# Host_Bypass_FPGA_3V3.net
KiCad netlist of a schematic drawn in Altium Designer
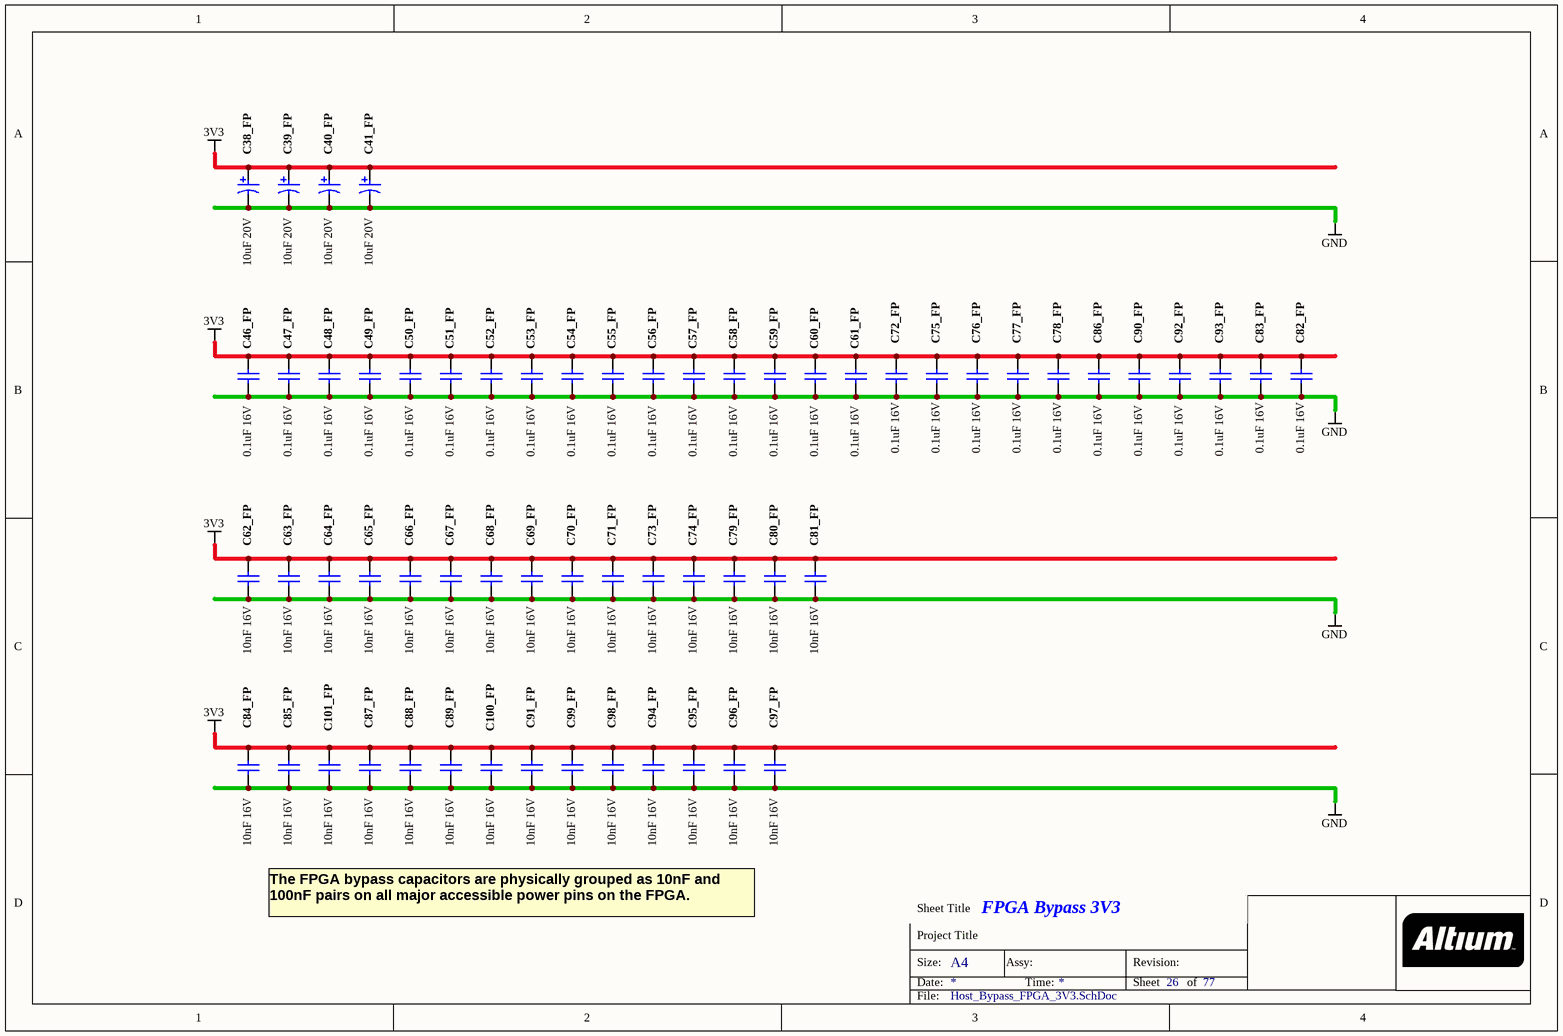
[diagram p0: Host_Bypass_FPGA_3V3.SchDoc]

(export (version "E")
  (design (tool "Eeschema 10.0.6"))
  (components
    (comp (ref "C38_FP")
      (value "10uF 20V")
      (footprint "CAPC3528-STAR")
      (description "Capacitor, Tantalum, 10uF 10% 20V MCCT-B (3528)")
      (fields (field (name "TOLERANCE") "10 %"))
      (libsource (lib "altium-import") (part "root_0_CAP-P_"))
    )
    (comp (ref "C39_FP")
      (value "10uF 20V")
      (footprint "CAPC3528-STAR")
      (description "Capacitor, Tantalum, 10uF 10% 20V MCCT-B (3528)")
      (fields (field (name "TOLERANCE") "10 %"))
      (libsource (lib "altium-import") (part "root_0_CAP-P_"))
    )
    (comp (ref "C40_FP")
      (value "10uF 20V")
      (footprint "CAPC3528-STAR")
      (description "Capacitor, Tantalum, 10uF 10% 20V MCCT-B (3528)")
      (fields (field (name "TOLERANCE") "10 %"))
      (libsource (lib "altium-import") (part "root_0_CAP-P_"))
    )
    (comp (ref "C41_FP")
      (value "10uF 20V")
      (footprint "CAPC3528-STAR")
      (description "Capacitor, Tantalum, 10uF 10% 20V MCCT-B (3528)")
      (fields (field (name "TOLERANCE") "10 %"))
      (libsource (lib "altium-import") (part "root_0_CAP-P_"))
    )
    (comp (ref "C46_FP")
      (value "0.1uF 16V")
      (footprint "CAPC1005-STAR")
      (description "Capacitor, Ceramic, 0.1uF 10% 16V 0402 (1005) X7R")
      (fields (field (name "TOLERANCE") "10 %"))
      (libsource (lib "altium-import") (part "root_0_mirrored_CAP-NP_"))
    )
    (comp (ref "C47_FP")
      (value "0.1uF 16V")
      (footprint "CAPC1005-STAR")
      (description "Capacitor, Ceramic, 0.1uF 10% 16V 0402 (1005) X7R")
      (fields (field (name "TOLERANCE") "10 %"))
      (libsource (lib "altium-import") (part "root_0_mirrored_CAP-NP_"))
    )
    (comp (ref "C48_FP")
      (value "0.1uF 16V")
      (footprint "CAPC1005-STAR")
      (description "Capacitor, Ceramic, 0.1uF 10% 16V 0402 (1005) X7R")
      (fields (field (name "TOLERANCE") "10 %"))
      (libsource (lib "altium-import") (part "root_0_mirrored_CAP-NP_"))
    )
    (comp (ref "C49_FP")
      (value "0.1uF 16V")
      (footprint "CAPC1005-STAR")
      (description "Capacitor, Ceramic, 0.1uF 10% 16V 0402 (1005) X7R")
      (fields (field (name "TOLERANCE") "10 %"))
      (libsource (lib "altium-import") (part "root_0_mirrored_CAP-NP_"))
    )
    (comp (ref "C50_FP")
      (value "0.1uF 16V")
      (footprint "CAPC1005-STAR")
      (description "Capacitor, Ceramic, 0.1uF 10% 16V 0402 (1005) X7R")
      (fields (field (name "TOLERANCE") "10 %"))
      (libsource (lib "altium-import") (part "root_0_mirrored_CAP-NP_"))
    )
    (comp (ref "C51_FP")
      (value "0.1uF 16V")
      (footprint "CAPC1005-STAR")
      (description "Capacitor, Ceramic, 0.1uF 10% 16V 0402 (1005) X7R")
      (fields (field (name "TOLERANCE") "10 %"))
      (libsource (lib "altium-import") (part "root_0_mirrored_CAP-NP_"))
    )
    (comp (ref "C52_FP")
      (value "0.1uF 16V")
      (footprint "CAPC1005-STAR")
      (description "Capacitor, Ceramic, 0.1uF 10% 16V 0402 (1005) X7R")
      (fields (field (name "TOLERANCE") "10 %"))
      (libsource (lib "altium-import") (part "root_0_mirrored_CAP-NP_"))
    )
    (comp (ref "C53_FP")
      (value "0.1uF 16V")
      (footprint "CAPC1005-STAR")
      (description "Capacitor, Ceramic, 0.1uF 10% 16V 0402 (1005) X7R")
      (fields (field (name "TOLERANCE") "10 %"))
      (libsource (lib "altium-import") (part "root_0_mirrored_CAP-NP_"))
    )
    (comp (ref "C54_FP")
      (value "0.1uF 16V")
      (footprint "CAPC1005-STAR")
      (description "Capacitor, Ceramic, 0.1uF 10% 16V 0402 (1005) X7R")
      (fields (field (name "TOLERANCE") "10 %"))
      (libsource (lib "altium-import") (part "root_0_mirrored_CAP-NP_"))
    )
    (comp (ref "C55_FP")
      (value "0.1uF 16V")
      (footprint "CAPC1005-STAR")
      (description "Capacitor, Ceramic, 0.1uF 10% 16V 0402 (1005) X7R")
      (fields (field (name "TOLERANCE") "10 %"))
      (libsource (lib "altium-import") (part "root_0_mirrored_CAP-NP_"))
    )
    (comp (ref "C56_FP")
      (value "0.1uF 16V")
      (footprint "CAPC1005-STAR")
      (description "Capacitor, Ceramic, 0.1uF 10% 16V 0402 (1005) X7R")
      (fields (field (name "TOLERANCE") "10 %"))
      (libsource (lib "altium-import") (part "root_0_mirrored_CAP-NP_"))
    )
    (comp (ref "C57_FP")
      (value "0.1uF 16V")
      (footprint "CAPC1005-STAR")
      (description "Capacitor, Ceramic, 0.1uF 10% 16V 0402 (1005) X7R")
      (fields (field (name "TOLERANCE") "10 %"))
      (libsource (lib "altium-import") (part "root_0_mirrored_CAP-NP_"))
    )
    (comp (ref "C58_FP")
      (value "0.1uF 16V")
      (footprint "CAPC1005-STAR")
      (description "Capacitor, Ceramic, 0.1uF 10% 16V 0402 (1005) X7R")
      (fields (field (name "TOLERANCE") "10 %"))
      (libsource (lib "altium-import") (part "root_0_mirrored_CAP-NP_"))
    )
    (comp (ref "C59_FP")
      (value "0.1uF 16V")
      (footprint "CAPC1005-STAR")
      (description "Capacitor, Ceramic, 0.1uF 10% 16V 0402 (1005) X7R")
      (fields (field (name "TOLERANCE") "10 %"))
      (libsource (lib "altium-import") (part "root_0_mirrored_CAP-NP_"))
    )
    (comp (ref "C60_FP")
      (value "0.1uF 16V")
      (footprint "CAPC1005-STAR")
      (description "Capacitor, Ceramic, 0.1uF 10% 16V 0402 (1005) X7R")
      (fields (field (name "TOLERANCE") "10 %"))
      (libsource (lib "altium-import") (part "root_0_mirrored_CAP-NP_"))
    )
    (comp (ref "C61_FP")
      (value "0.1uF 16V")
      (footprint "CAPC1005-STAR")
      (description "Capacitor, Ceramic, 0.1uF 10% 16V 0402 (1005) X7R")
      (fields (field (name "TOLERANCE") "10 %"))
      (libsource (lib "altium-import") (part "root_0_mirrored_CAP-NP_"))
    )
    (comp (ref "C62_FP")
      (value "10nF 16V")
      (footprint "CAPC1005-STAR")
      (description "Capacitor, Ceramic, 10nF 10% 16V 0402 (1005) X7R")
      (fields (field (name "TOLERANCE") "10 %"))
      (libsource (lib "altium-import") (part "root_0_CAP-NP_"))
    )
    (comp (ref "C63_FP")
      (value "10nF 16V")
      (footprint "CAPC1005-STAR")
      (description "Capacitor, Ceramic, 10nF 10% 16V 0402 (1005) X7R")
      (fields (field (name "TOLERANCE") "10 %"))
      (libsource (lib "altium-import") (part "root_0_CAP-NP_"))
    )
    (comp (ref "C64_FP")
      (value "10nF 16V")
      (footprint "CAPC1005-STAR")
      (description "Capacitor, Ceramic, 10nF 10% 16V 0402 (1005) X7R")
      (fields (field (name "TOLERANCE") "10 %"))
      (libsource (lib "altium-import") (part "root_0_CAP-NP_"))
    )
    (comp (ref "C65_FP")
      (value "10nF 16V")
      (footprint "CAPC1005-STAR")
      (description "Capacitor, Ceramic, 10nF 10% 16V 0402 (1005) X7R")
      (fields (field (name "TOLERANCE") "10 %"))
      (libsource (lib "altium-import") (part "root_0_CAP-NP_"))
    )
    (comp (ref "C66_FP")
      (value "10nF 16V")
      (footprint "CAPC1005-STAR")
      (description "Capacitor, Ceramic, 10nF 10% 16V 0402 (1005) X7R")
      (fields (field (name "TOLERANCE") "10 %"))
      (libsource (lib "altium-import") (part "root_0_CAP-NP_"))
    )
    (comp (ref "C67_FP")
      (value "10nF 16V")
      (footprint "CAPC1005-STAR")
      (description "Capacitor, Ceramic, 10nF 10% 16V 0402 (1005) X7R")
      (fields (field (name "TOLERANCE") "10 %"))
      (libsource (lib "altium-import") (part "root_0_CAP-NP_"))
    )
    (comp (ref "C68_FP")
      (value "10nF 16V")
      (footprint "CAPC1005-STAR")
      (description "Capacitor, Ceramic, 10nF 10% 16V 0402 (1005) X7R")
      (fields (field (name "TOLERANCE") "10 %"))
      (libsource (lib "altium-import") (part "root_0_CAP-NP_"))
    )
    (comp (ref "C69_FP")
      (value "10nF 16V")
      (footprint "CAPC1005-STAR")
      (description "Capacitor, Ceramic, 10nF 10% 16V 0402 (1005) X7R")
      (fields (field (name "TOLERANCE") "10 %"))
      (libsource (lib "altium-import") (part "root_0_CAP-NP_"))
    )
    (comp (ref "C70_FP")
      (value "10nF 16V")
      (footprint "CAPC1005-STAR")
      (description "Capacitor, Ceramic, 10nF 10% 16V 0402 (1005) X7R")
      (fields (field (name "TOLERANCE") "10 %"))
      (libsource (lib "altium-import") (part "root_0_CAP-NP_"))
    )
    (comp (ref "C71_FP")
      (value "10nF 16V")
      (footprint "CAPC1005-STAR")
      (description "Capacitor, Ceramic, 10nF 10% 16V 0402 (1005) X7R")
      (fields (field (name "TOLERANCE") "10 %"))
      (libsource (lib "altium-import") (part "root_0_CAP-NP_"))
    )
    (comp (ref "C72_FP")
      (value "0.1uF 16V")
      (footprint "CAPC1005-STAR")
      (description "Capacitor, Ceramic, 0.1uF 10% 16V 0402 (1005) X7R")
      (fields (field (name "TOLERANCE") "10 %"))
      (libsource (lib "AltiumDesignLibrary") (part "CAP-NP"))
    )
    (comp (ref "C73_FP")
      (value "10nF 16V")
      (footprint "CAPC1005-STAR")
      (description "Capacitor, Ceramic, 10nF 10% 16V 0402 (1005) X7R")
      (fields (field (name "TOLERANCE") "10 %"))
      (libsource (lib "altium-import") (part "root_0_CAP-NP_"))
    )
    (comp (ref "C74_FP")
      (value "10nF 16V")
      (footprint "CAPC1005-STAR")
      (description "Capacitor, Ceramic, 10nF 10% 16V 0402 (1005) X7R")
      (fields (field (name "TOLERANCE") "10 %"))
      (libsource (lib "altium-import") (part "root_0_CAP-NP_"))
    )
    (comp (ref "C75_FP")
      (value "0.1uF 16V")
      (footprint "CAPC1005-STAR")
      (description "Capacitor, Ceramic, 0.1uF 10% 16V 0402 (1005) X7R")
      (fields (field (name "TOLERANCE") "10 %"))
      (libsource (lib "AltiumDesignLibrary") (part "CAP-NP"))
    )
    (comp (ref "C76_FP")
      (value "0.1uF 16V")
      (footprint "CAPC1005-STAR")
      (description "Capacitor, Ceramic, 0.1uF 10% 16V 0402 (1005) X7R")
      (fields (field (name "TOLERANCE") "10 %"))
      (libsource (lib "AltiumDesignLibrary") (part "CAP-NP"))
    )
    (comp (ref "C77_FP")
      (value "0.1uF 16V")
      (footprint "CAPC1005-STAR")
      (description "Capacitor, Ceramic, 0.1uF 10% 16V 0402 (1005) X7R")
      (fields (field (name "TOLERANCE") "10 %"))
      (libsource (lib "AltiumDesignLibrary") (part "CAP-NP"))
    )
    (comp (ref "C78_FP")
      (value "0.1uF 16V")
      (footprint "CAPC1005-STAR")
      (description "Capacitor, Ceramic, 0.1uF 10% 16V 0402 (1005) X7R")
      (fields (field (name "TOLERANCE") "10 %"))
      (libsource (lib "AltiumDesignLibrary") (part "CAP-NP"))
    )
    (comp (ref "C79_FP")
      (value "10nF 16V")
      (footprint "CAPC1005-STAR")
      (description "Capacitor, Ceramic, 10nF 10% 16V 0402 (1005) X7R")
      (fields (field (name "TOLERANCE") "10 %"))
      (libsource (lib "altium-import") (part "root_0_CAP-NP_"))
    )
    (comp (ref "C80_FP")
      (value "10nF 16V")
      (footprint "CAPC1005-STAR")
      (description "Capacitor, Ceramic, 10nF 10% 16V 0402 (1005) X7R")
      (fields (field (name "TOLERANCE") "10 %"))
      (libsource (lib "altium-import") (part "root_0_CAP-NP_"))
    )
    (comp (ref "C81_FP")
      (value "10nF 16V")
      (footprint "CAPC1005-STAR")
      (description "Capacitor, Ceramic, 10nF 10% 16V 0402 (1005) X7R")
      (fields (field (name "TOLERANCE") "10 %"))
      (libsource (lib "altium-import") (part "root_0_CAP-NP_"))
    )
    (comp (ref "C82_FP")
      (value "0.1uF 16V")
      (footprint "CAPC1005-STAR")
      (description "Capacitor, Ceramic, 0.1uF 10% 16V 0402 (1005) X7R")
      (fields (field (name "TOLERANCE") "10 %"))
      (libsource (lib "AltiumDesignLibrary") (part "CAP-NP"))
    )
    (comp (ref "C83_FP")
      (value "0.1uF 16V")
      (footprint "CAPC1005-STAR")
      (description "Capacitor, Ceramic, 0.1uF 10% 16V 0402 (1005) X7R")
      (fields (field (name "TOLERANCE") "10 %"))
      (libsource (lib "AltiumDesignLibrary") (part "CAP-NP"))
    )
    (comp (ref "C84_FP")
      (value "10nF 16V")
      (footprint "CAPC1005-STAR")
      (description "Capacitor, Ceramic, 10nF 10% 16V 0402 (1005) X7R")
      (fields (field (name "TOLERANCE") "10 %"))
      (libsource (lib "altium-import") (part "root_0_CAP-NP_"))
    )
    (comp (ref "C85_FP")
      (value "10nF 16V")
      (footprint "CAPC1005-STAR")
      (description "Capacitor, Ceramic, 10nF 10% 16V 0402 (1005) X7R")
      (fields (field (name "TOLERANCE") "10 %"))
      (libsource (lib "altium-import") (part "root_0_CAP-NP_"))
    )
    (comp (ref "C86_FP")
      (value "0.1uF 16V")
      (footprint "CAPC1005-STAR")
      (description "Capacitor, Ceramic, 0.1uF 10% 16V 0402 (1005) X7R")
      (fields (field (name "TOLERANCE") "10 %"))
      (libsource (lib "AltiumDesignLibrary") (part "CAP-NP"))
    )
    (comp (ref "C87_FP")
      (value "10nF 16V")
      (footprint "CAPC1005-STAR")
      (description "Capacitor, Ceramic, 10nF 10% 16V 0402 (1005) X7R")
      (fields (field (name "TOLERANCE") "10 %"))
      (libsource (lib "altium-import") (part "root_0_CAP-NP_"))
    )
    (comp (ref "C88_FP")
      (value "10nF 16V")
      (footprint "CAPC1005-STAR")
      (description "Capacitor, Ceramic, 10nF 10% 16V 0402 (1005) X7R")
      (fields (field (name "TOLERANCE") "10 %"))
      (libsource (lib "altium-import") (part "root_0_CAP-NP_"))
    )
    (comp (ref "C89_FP")
      (value "10nF 16V")
      (footprint "CAPC1005-STAR")
      (description "Capacitor, Ceramic, 10nF 10% 16V 0402 (1005) X7R")
      (fields (field (name "TOLERANCE") "10 %"))
      (libsource (lib "altium-import") (part "root_0_CAP-NP_"))
    )
    (comp (ref "C90_FP")
      (value "0.1uF 16V")
      (footprint "CAPC1005-STAR")
      (description "Capacitor, Ceramic, 0.1uF 10% 16V 0402 (1005) X7R")
      (fields (field (name "TOLERANCE") "10 %"))
      (libsource (lib "AltiumDesignLibrary") (part "CAP-NP"))
    )
    (comp (ref "C91_FP")
      (value "10nF 16V")
      (footprint "CAPC1005-STAR")
      (description "Capacitor, Ceramic, 10nF 10% 16V 0402 (1005) X7R")
      (fields (field (name "TOLERANCE") "10 %"))
      (libsource (lib "altium-import") (part "root_0_CAP-NP_"))
    )
    (comp (ref "C92_FP")
      (value "0.1uF 16V")
      (footprint "CAPC1005-STAR")
      (description "Capacitor, Ceramic, 0.1uF 10% 16V 0402 (1005) X7R")
      (fields (field (name "TOLERANCE") "10 %"))
      (libsource (lib "AltiumDesignLibrary") (part "CAP-NP"))
    )
    (comp (ref "C93_FP")
      (value "0.1uF 16V")
      (footprint "CAPC1005-STAR")
      (description "Capacitor, Ceramic, 0.1uF 10% 16V 0402 (1005) X7R")
      (fields (field (name "TOLERANCE") "10 %"))
      (libsource (lib "AltiumDesignLibrary") (part "CAP-NP"))
    )
    (comp (ref "C94_FP")
      (value "10nF 16V")
      (footprint "CAPC1005-STAR")
      (description "Capacitor, Ceramic, 10nF 10% 16V 0402 (1005) X7R")
      (fields (field (name "TOLERANCE") "10 %"))
      (libsource (lib "altium-import") (part "root_0_CAP-NP_"))
    )
    (comp (ref "C95_FP")
      (value "10nF 16V")
      (footprint "CAPC1005-STAR")
      (description "Capacitor, Ceramic, 10nF 10% 16V 0402 (1005) X7R")
      (fields (field (name "TOLERANCE") "10 %"))
      (libsource (lib "altium-import") (part "root_0_CAP-NP_"))
    )
    (comp (ref "C96_FP")
      (value "10nF 16V")
      (footprint "CAPC1005-STAR")
      (description "Capacitor, Ceramic, 10nF 10% 16V 0402 (1005) X7R")
      (fields (field (name "TOLERANCE") "10 %"))
      (libsource (lib "altium-import") (part "root_0_CAP-NP_"))
    )
    (comp (ref "C97_FP")
      (value "10nF 16V")
      (footprint "CAPC1005-STAR")
      (description "Capacitor, Ceramic, 10nF 10% 16V 0402 (1005) X7R")
      (fields (field (name "TOLERANCE") "10 %"))
      (libsource (lib "altium-import") (part "root_0_CAP-NP_"))
    )
    (comp (ref "C98_FP")
      (value "10nF 16V")
      (footprint "CAPC1005-STAR")
      (description "Capacitor, Ceramic, 10nF 10% 16V 0402 (1005) X7R")
      (fields (field (name "TOLERANCE") "10 %"))
      (libsource (lib "altium-import") (part "root_0_CAP-NP_"))
    )
    (comp (ref "C99_FP")
      (value "10nF 16V")
      (footprint "CAPC1005-STAR")
      (description "Capacitor, Ceramic, 10nF 10% 16V 0402 (1005) X7R")
      (fields (field (name "TOLERANCE") "10 %"))
      (libsource (lib "altium-import") (part "root_0_CAP-NP_"))
    )
    (comp (ref "C100_FP")
      (value "10nF 16V")
      (footprint "CAPC1005-STAR")
      (description "Capacitor, Ceramic, 10nF 10% 16V 0402 (1005) X7R")
      (fields (field (name "TOLERANCE") "10 %"))
      (libsource (lib "altium-import") (part "root_0_CAP-NP_"))
    )
    (comp (ref "C101_FP")
      (value "10nF 16V")
      (footprint "CAPC1005-STAR")
      (description "Capacitor, Ceramic, 10nF 10% 16V 0402 (1005) X7R")
      (fields (field (name "TOLERANCE") "10 %"))
      (libsource (lib "altium-import") (part "root_0_CAP-NP_"))
    )
  )
  (nets
    (net (code "1") (name "3V3") (class "Default")
      (node (ref "C100_FP") (pin "1") (pinfunction "1_1") (pintype "passive"))
      (node (ref "C101_FP") (pin "1") (pinfunction "1_1") (pintype "passive"))
      (node (ref "C38_FP") (pin "1") (pinfunction "1_1") (pintype "passive"))
      (node (ref "C39_FP") (pin "1") (pinfunction "1_1") (pintype "passive"))
      (node (ref "C40_FP") (pin "1") (pinfunction "1_1") (pintype "passive"))
      (node (ref "C41_FP") (pin "1") (pinfunction "1_1") (pintype "passive"))
      (node (ref "C46_FP") (pin "1") (pinfunction "1_1") (pintype "passive"))
      (node (ref "C47_FP") (pin "1") (pinfunction "1_1") (pintype "passive"))
      (node (ref "C48_FP") (pin "1") (pinfunction "1_1") (pintype "passive"))
      (node (ref "C49_FP") (pin "1") (pinfunction "1_1") (pintype "passive"))
      (node (ref "C50_FP") (pin "1") (pinfunction "1_1") (pintype "passive"))
      (node (ref "C51_FP") (pin "1") (pinfunction "1_1") (pintype "passive"))
      (node (ref "C52_FP") (pin "1") (pinfunction "1_1") (pintype "passive"))
      (node (ref "C53_FP") (pin "1") (pinfunction "1_1") (pintype "passive"))
      (node (ref "C54_FP") (pin "1") (pinfunction "1_1") (pintype "passive"))
      (node (ref "C55_FP") (pin "1") (pinfunction "1_1") (pintype "passive"))
      (node (ref "C56_FP") (pin "1") (pinfunction "1_1") (pintype "passive"))
      (node (ref "C57_FP") (pin "1") (pinfunction "1_1") (pintype "passive"))
      (node (ref "C58_FP") (pin "1") (pinfunction "1_1") (pintype "passive"))
      (node (ref "C59_FP") (pin "1") (pinfunction "1_1") (pintype "passive"))
      (node (ref "C60_FP") (pin "1") (pinfunction "1_1") (pintype "passive"))
      (node (ref "C61_FP") (pin "1") (pinfunction "1_1") (pintype "passive"))
      (node (ref "C62_FP") (pin "1") (pinfunction "1_1") (pintype "passive"))
      (node (ref "C63_FP") (pin "1") (pinfunction "1_1") (pintype "passive"))
      (node (ref "C64_FP") (pin "1") (pinfunction "1_1") (pintype "passive"))
      (node (ref "C65_FP") (pin "1") (pinfunction "1_1") (pintype "passive"))
      (node (ref "C66_FP") (pin "1") (pinfunction "1_1") (pintype "passive"))
      (node (ref "C67_FP") (pin "1") (pinfunction "1_1") (pintype "passive"))
      (node (ref "C68_FP") (pin "1") (pinfunction "1_1") (pintype "passive"))
      (node (ref "C69_FP") (pin "1") (pinfunction "1_1") (pintype "passive"))
      (node (ref "C70_FP") (pin "1") (pinfunction "1_1") (pintype "passive"))
      (node (ref "C71_FP") (pin "1") (pinfunction "1_1") (pintype "passive"))
      (node (ref "C72_FP") (pin "1") (pinfunction "1_1") (pintype "passive"))
      (node (ref "C73_FP") (pin "1") (pinfunction "1_1") (pintype "passive"))
      (node (ref "C74_FP") (pin "1") (pinfunction "1_1") (pintype "passive"))
      (node (ref "C75_FP") (pin "1") (pinfunction "1_1") (pintype "passive"))
      (node (ref "C76_FP") (pin "1") (pinfunction "1_1") (pintype "passive"))
      (node (ref "C77_FP") (pin "1") (pinfunction "1_1") (pintype "passive"))
      (node (ref "C78_FP") (pin "1") (pinfunction "1_1") (pintype "passive"))
      (node (ref "C79_FP") (pin "1") (pinfunction "1_1") (pintype "passive"))
      (node (ref "C80_FP") (pin "1") (pinfunction "1_1") (pintype "passive"))
      (node (ref "C81_FP") (pin "1") (pinfunction "1_1") (pintype "passive"))
      (node (ref "C82_FP") (pin "1") (pinfunction "1_1") (pintype "passive"))
      (node (ref "C83_FP") (pin "1") (pinfunction "1_1") (pintype "passive"))
      (node (ref "C84_FP") (pin "1") (pinfunction "1_1") (pintype "passive"))
      (node (ref "C85_FP") (pin "1") (pinfunction "1_1") (pintype "passive"))
      (node (ref "C86_FP") (pin "1") (pinfunction "1_1") (pintype "passive"))
      (node (ref "C87_FP") (pin "1") (pinfunction "1_1") (pintype "passive"))
      (node (ref "C88_FP") (pin "1") (pinfunction "1_1") (pintype "passive"))
      (node (ref "C89_FP") (pin "1") (pinfunction "1_1") (pintype "passive"))
      (node (ref "C90_FP") (pin "1") (pinfunction "1_1") (pintype "passive"))
      (node (ref "C91_FP") (pin "1") (pinfunction "1_1") (pintype "passive"))
      (node (ref "C92_FP") (pin "1") (pinfunction "1_1") (pintype "passive"))
      (node (ref "C93_FP") (pin "1") (pinfunction "1_1") (pintype "passive"))
      (node (ref "C94_FP") (pin "1") (pinfunction "1_1") (pintype "passive"))
      (node (ref "C95_FP") (pin "1") (pinfunction "1_1") (pintype "passive"))
      (node (ref "C96_FP") (pin "1") (pinfunction "1_1") (pintype "passive"))
      (node (ref "C97_FP") (pin "1") (pinfunction "1_1") (pintype "passive"))
      (node (ref "C98_FP") (pin "1") (pinfunction "1_1") (pintype "passive"))
      (node (ref "C99_FP") (pin "1") (pinfunction "1_1") (pintype "passive"))
    )
    (net (code "2") (name "GND") (class "Default")
      (node (ref "C100_FP") (pin "2") (pinfunction "2_2") (pintype "passive"))
      (node (ref "C101_FP") (pin "2") (pinfunction "2_2") (pintype "passive"))
      (node (ref "C38_FP") (pin "2") (pinfunction "2_2") (pintype "passive"))
      (node (ref "C39_FP") (pin "2") (pinfunction "2_2") (pintype "passive"))
      (node (ref "C40_FP") (pin "2") (pinfunction "2_2") (pintype "passive"))
      (node (ref "C41_FP") (pin "2") (pinfunction "2_2") (pintype "passive"))
      (node (ref "C46_FP") (pin "2") (pinfunction "2_2") (pintype "passive"))
      (node (ref "C47_FP") (pin "2") (pinfunction "2_2") (pintype "passive"))
      (node (ref "C48_FP") (pin "2") (pinfunction "2_2") (pintype "passive"))
      (node (ref "C49_FP") (pin "2") (pinfunction "2_2") (pintype "passive"))
      (node (ref "C50_FP") (pin "2") (pinfunction "2_2") (pintype "passive"))
      (node (ref "C51_FP") (pin "2") (pinfunction "2_2") (pintype "passive"))
      (node (ref "C52_FP") (pin "2") (pinfunction "2_2") (pintype "passive"))
      (node (ref "C53_FP") (pin "2") (pinfunction "2_2") (pintype "passive"))
      (node (ref "C54_FP") (pin "2") (pinfunction "2_2") (pintype "passive"))
      (node (ref "C55_FP") (pin "2") (pinfunction "2_2") (pintype "passive"))
      (node (ref "C56_FP") (pin "2") (pinfunction "2_2") (pintype "passive"))
      (node (ref "C57_FP") (pin "2") (pinfunction "2_2") (pintype "passive"))
      (node (ref "C58_FP") (pin "2") (pinfunction "2_2") (pintype "passive"))
      (node (ref "C59_FP") (pin "2") (pinfunction "2_2") (pintype "passive"))
      (node (ref "C60_FP") (pin "2") (pinfunction "2_2") (pintype "passive"))
      (node (ref "C61_FP") (pin "2") (pinfunction "2_2") (pintype "passive"))
      (node (ref "C62_FP") (pin "2") (pinfunction "2_2") (pintype "passive"))
      (node (ref "C63_FP") (pin "2") (pinfunction "2_2") (pintype "passive"))
      (node (ref "C64_FP") (pin "2") (pinfunction "2_2") (pintype "passive"))
      (node (ref "C65_FP") (pin "2") (pinfunction "2_2") (pintype "passive"))
      (node (ref "C66_FP") (pin "2") (pinfunction "2_2") (pintype "passive"))
      (node (ref "C67_FP") (pin "2") (pinfunction "2_2") (pintype "passive"))
      (node (ref "C68_FP") (pin "2") (pinfunction "2_2") (pintype "passive"))
      (node (ref "C69_FP") (pin "2") (pinfunction "2_2") (pintype "passive"))
      (node (ref "C70_FP") (pin "2") (pinfunction "2_2") (pintype "passive"))
      (node (ref "C71_FP") (pin "2") (pinfunction "2_2") (pintype "passive"))
      (node (ref "C72_FP") (pin "2") (pinfunction "2_2") (pintype "passive"))
      (node (ref "C73_FP") (pin "2") (pinfunction "2_2") (pintype "passive"))
      (node (ref "C74_FP") (pin "2") (pinfunction "2_2") (pintype "passive"))
      (node (ref "C75_FP") (pin "2") (pinfunction "2_2") (pintype "passive"))
      (node (ref "C76_FP") (pin "2") (pinfunction "2_2") (pintype "passive"))
      (node (ref "C77_FP") (pin "2") (pinfunction "2_2") (pintype "passive"))
      (node (ref "C78_FP") (pin "2") (pinfunction "2_2") (pintype "passive"))
      (node (ref "C79_FP") (pin "2") (pinfunction "2_2") (pintype "passive"))
      (node (ref "C80_FP") (pin "2") (pinfunction "2_2") (pintype "passive"))
      (node (ref "C81_FP") (pin "2") (pinfunction "2_2") (pintype "passive"))
      (node (ref "C82_FP") (pin "2") (pinfunction "2_2") (pintype "passive"))
      (node (ref "C83_FP") (pin "2") (pinfunction "2_2") (pintype "passive"))
      (node (ref "C84_FP") (pin "2") (pinfunction "2_2") (pintype "passive"))
      (node (ref "C85_FP") (pin "2") (pinfunction "2_2") (pintype "passive"))
      (node (ref "C86_FP") (pin "2") (pinfunction "2_2") (pintype "passive"))
      (node (ref "C87_FP") (pin "2") (pinfunction "2_2") (pintype "passive"))
      (node (ref "C88_FP") (pin "2") (pinfunction "2_2") (pintype "passive"))
      (node (ref "C89_FP") (pin "2") (pinfunction "2_2") (pintype "passive"))
      (node (ref "C90_FP") (pin "2") (pinfunction "2_2") (pintype "passive"))
      (node (ref "C91_FP") (pin "2") (pinfunction "2_2") (pintype "passive"))
      (node (ref "C92_FP") (pin "2") (pinfunction "2_2") (pintype "passive"))
      (node (ref "C93_FP") (pin "2") (pinfunction "2_2") (pintype "passive"))
      (node (ref "C94_FP") (pin "2") (pinfunction "2_2") (pintype "passive"))
      (node (ref "C95_FP") (pin "2") (pinfunction "2_2") (pintype "passive"))
      (node (ref "C96_FP") (pin "2") (pinfunction "2_2") (pintype "passive"))
      (node (ref "C97_FP") (pin "2") (pinfunction "2_2") (pintype "passive"))
      (node (ref "C98_FP") (pin "2") (pinfunction "2_2") (pintype "passive"))
      (node (ref "C99_FP") (pin "2") (pinfunction "2_2") (pintype "passive"))
    )
  )
)
